# POWER_SUPPLY.net
KiCad netlist of a schematic drawn in Altium Designer
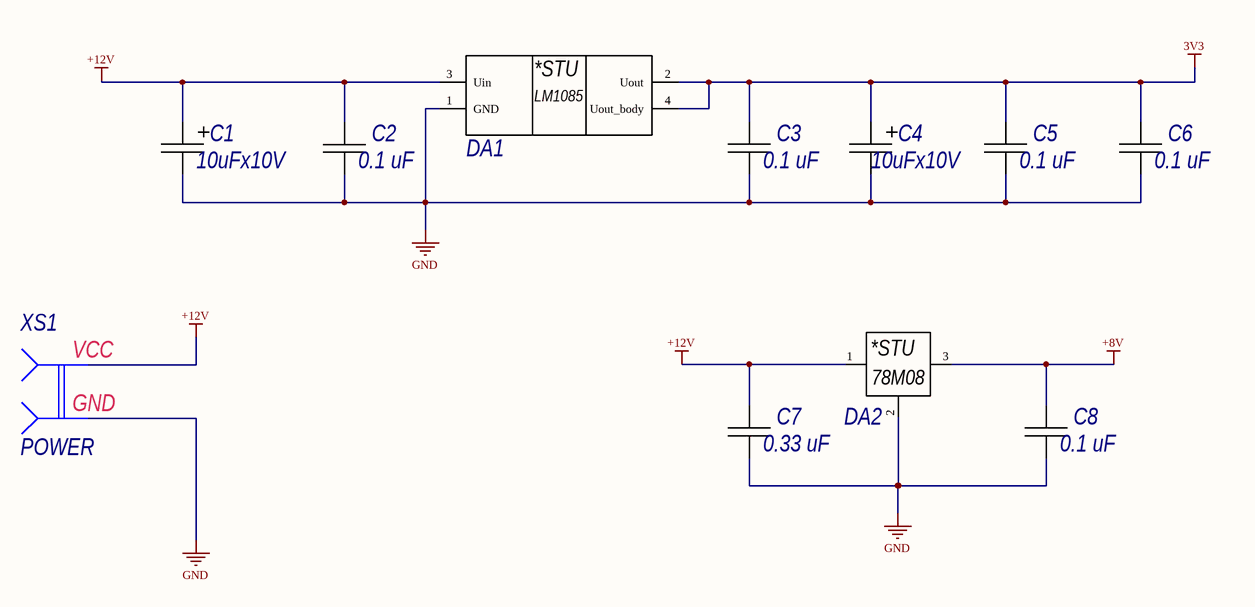
[diagram p0: POWER_SUPPLY.SchDoc]

(export (version "E")
  (design (tool "Eeschema 10.0.6"))
  (components
    (comp (ref "C1")
      (value "10uFx10V")
      (fields (field (name "PUBLISHER") "Andrew Danich"))
      (libsource (lib "PA_control_board") (part "CAP_TECAP_A"))
    )
    (comp (ref "C2")
      (value "0.1 uF")
      (footprint "C0805C")
      (fields (field (name "PUBLISHER") "Andrew Danich"))
      (libsource (lib "PA_control_board") (part "CAP_0805"))
    )
    (comp (ref "C3")
      (value "0.1 uF")
      (footprint "C0805C")
      (fields (field (name "PUBLISHER") "Andrew Danich"))
      (libsource (lib "PA_control_board") (part "CAP_0805"))
    )
    (comp (ref "C4")
      (value "10uFx10V")
      (fields (field (name "PUBLISHER") "Andrew Danich"))
      (libsource (lib "PA_control_board") (part "CAP_TECAP_A"))
    )
    (comp (ref "C5")
      (value "0.1 uF")
      (footprint "C0805C")
      (fields (field (name "PUBLISHER") "Andrew Danich"))
      (libsource (lib "PA_control_board") (part "CAP_0805"))
    )
    (comp (ref "C6")
      (value "0.1 uF")
      (footprint "C0805C")
      (fields (field (name "PUBLISHER") "Andrew Danich"))
      (libsource (lib "PA_control_board") (part "CAP_0805"))
    )
    (comp (ref "C7")
      (value "0.33 uF")
      (footprint "C0805C")
      (fields (field (name "PUBLISHER") "Andrew Danich"))
      (libsource (lib "PA_control_board") (part "CAP_0805"))
    )
    (comp (ref "C8")
      (value "0.1 uF")
      (footprint "C0805C")
      (fields (field (name "PUBLISHER") "Andrew Danich"))
      (libsource (lib "PA_control_board") (part "CAP_0805"))
    )
    (comp (ref "DA1")
      (value "LM1085ISX-3.3")
      (footprint "LM1085ISX-3.3")
      (fields (field (name "PUBLISHER") "Andrew Danich"))
      (libsource (lib "PA_control_board") (part "LM1085ISX-3.3"))
    )
    (comp (ref "DA2")
      (value "78M08CDT")
      (footprint "SC_TO-252AA")
      (fields (field (name "PUBLISHER") "Andrew Danich"))
      (libsource (lib "PA_control_board") (part "78M08CDT"))
    )
    (comp (ref "XS1")
      (value "POWER")
      (footprint "DG25C-B-02P-13")
      (fields (field (name "PUBLISHER") "Andrew Danich"))
      (libsource (lib "PA_control_board") (part "CONNECT_PW"))
    )
  )
  (nets
    (net (code "1") (name "+8V") (class "Default")
      (node (ref "C8") (pin "2") (pinfunction "2_2") (pintype "passive"))
      (node (ref "DA2") (pin "3") (pinfunction "Out_3") (pintype "passive"))
    )
    (net (code "2") (name "+12V") (class "Default")
      (node (ref "C1") (pin "1") (pinfunction "1_1") (pintype "passive"))
      (node (ref "C2") (pin "2") (pinfunction "2_2") (pintype "passive"))
      (node (ref "DA1") (pin "3") (pinfunction "Uin_3") (pintype "power_in"))
      (node (ref "DA2") (pin "1") (pinfunction "In_1") (pintype "passive"))
      (node (ref "XS1") (pin "2") (pintype "passive"))
    )
    (net (code "3") (name "3V3") (class "Default")
      (node (ref "C3") (pin "2") (pinfunction "2_2") (pintype "passive"))
      (node (ref "C4") (pin "1") (pinfunction "1_1") (pintype "passive"))
      (node (ref "C5") (pin "2") (pinfunction "2_2") (pintype "passive"))
      (node (ref "C6") (pin "2") (pinfunction "2_2") (pintype "passive"))
      (node (ref "DA1") (pin "2") (pinfunction "Uout_2") (pintype "power_in"))
      (node (ref "DA1") (pin "4") (pinfunction "Uout_body_4") (pintype "power_in"))
    )
    (net (code "4") (name "GND") (class "Default")
      (node (ref "C1") (pin "2") (pinfunction "2_2") (pintype "passive"))
      (node (ref "C2") (pin "1") (pinfunction "1_1") (pintype "passive"))
      (node (ref "C3") (pin "1") (pinfunction "1_1") (pintype "passive"))
      (node (ref "C4") (pin "2") (pinfunction "2_2") (pintype "passive"))
      (node (ref "C5") (pin "1") (pinfunction "1_1") (pintype "passive"))
      (node (ref "C6") (pin "1") (pinfunction "1_1") (pintype "passive"))
      (node (ref "C7") (pin "1") (pinfunction "1_1") (pintype "passive"))
      (node (ref "C8") (pin "1") (pinfunction "1_1") (pintype "passive"))
      (node (ref "DA1") (pin "1") (pinfunction "GND_1") (pintype "passive"))
      (node (ref "DA2") (pin "2") (pinfunction "GND_2") (pintype "passive"))
      (node (ref "XS1") (pin "1") (pintype "passive"))
    )
    (net (code "5") (name "unconnected-(C7-Pad2)") (class "Default")
      (node (ref "C7") (pin "2") (pinfunction "2_2") (pintype "passive"))
    )
  )
)
